# V1a.net
KiCad netlist of a schematic drawn in EAGLE
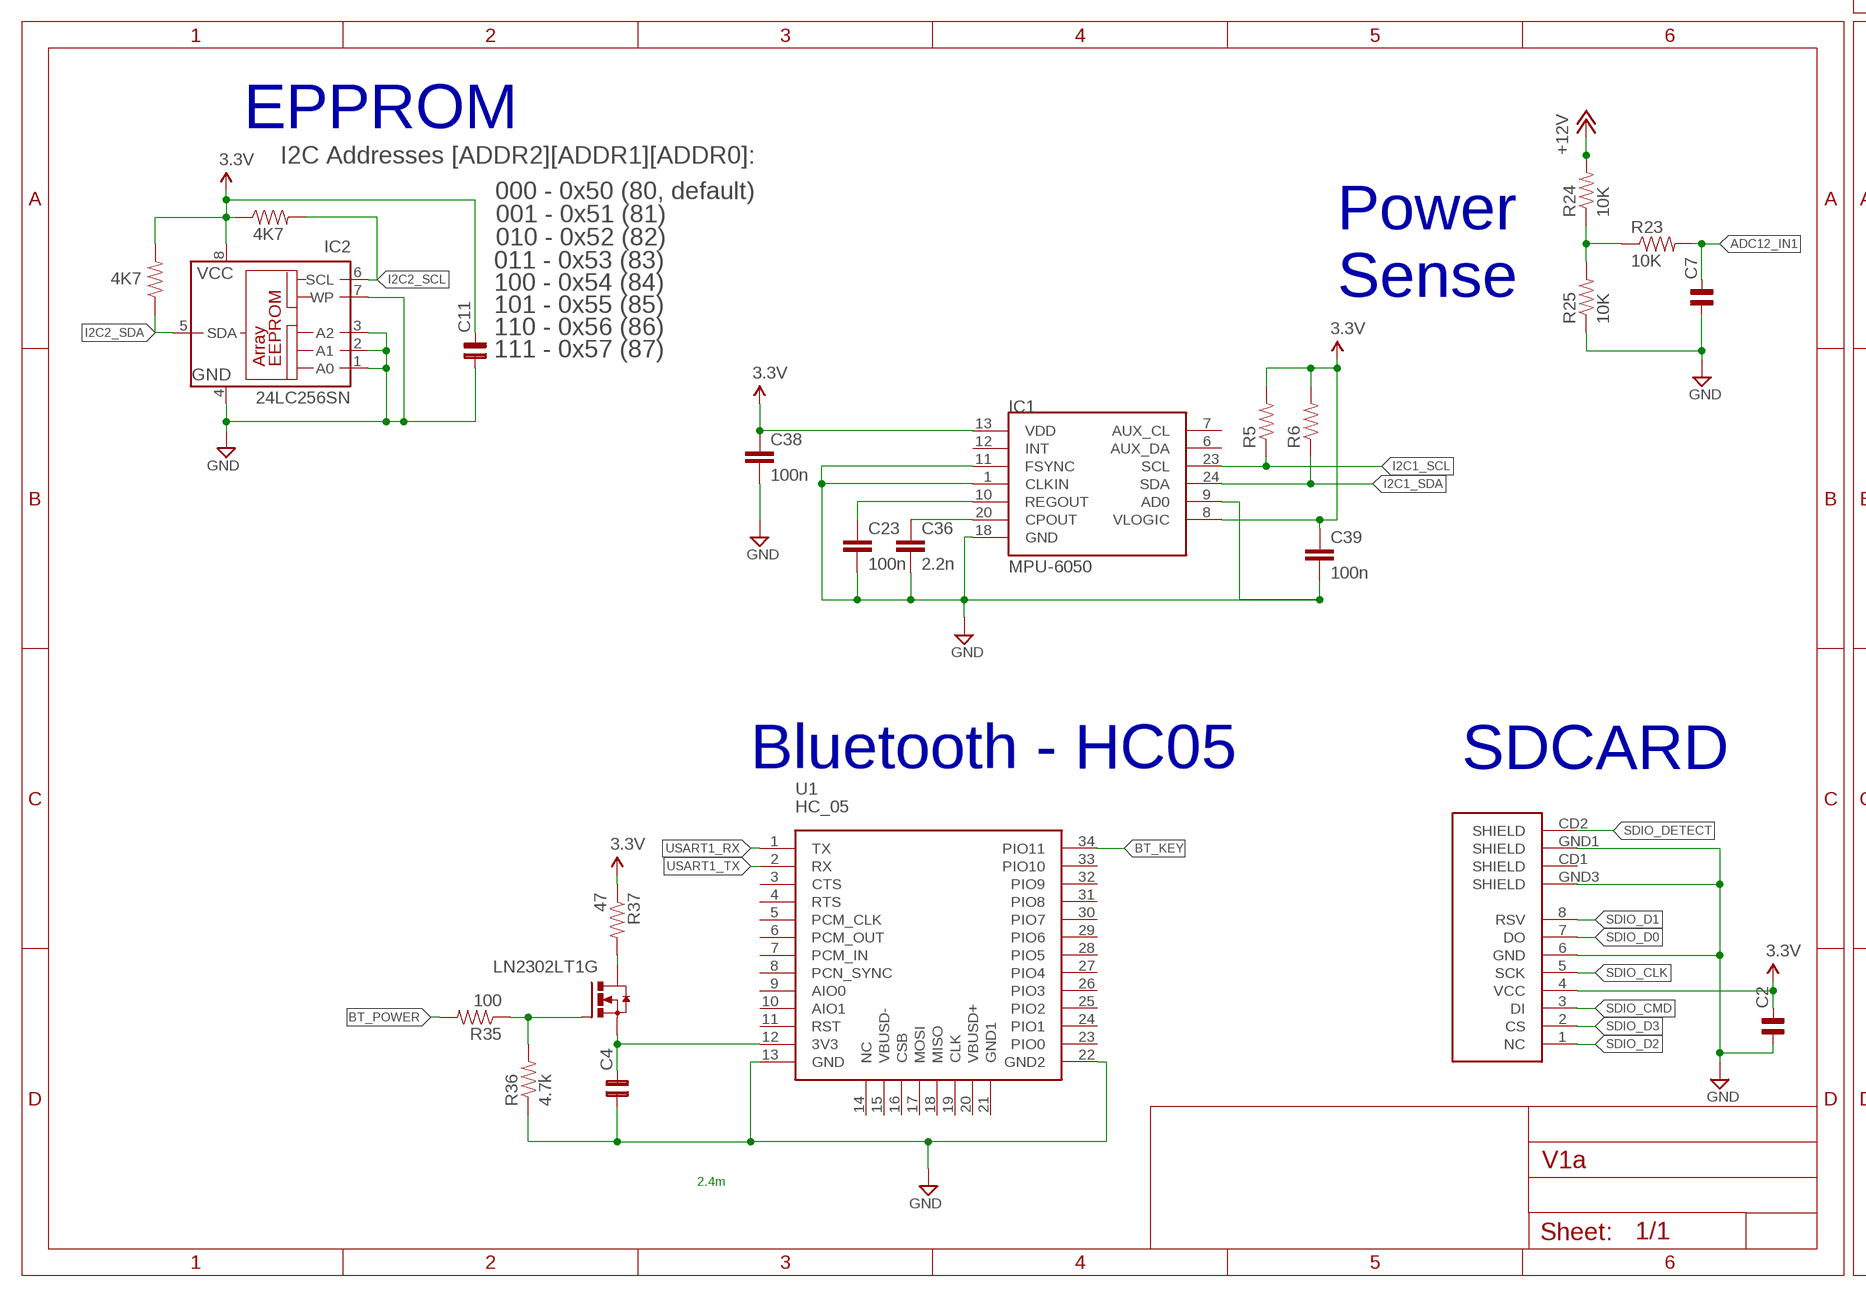
[diagram p0: schematic, sheet 1, part 1 of 2]
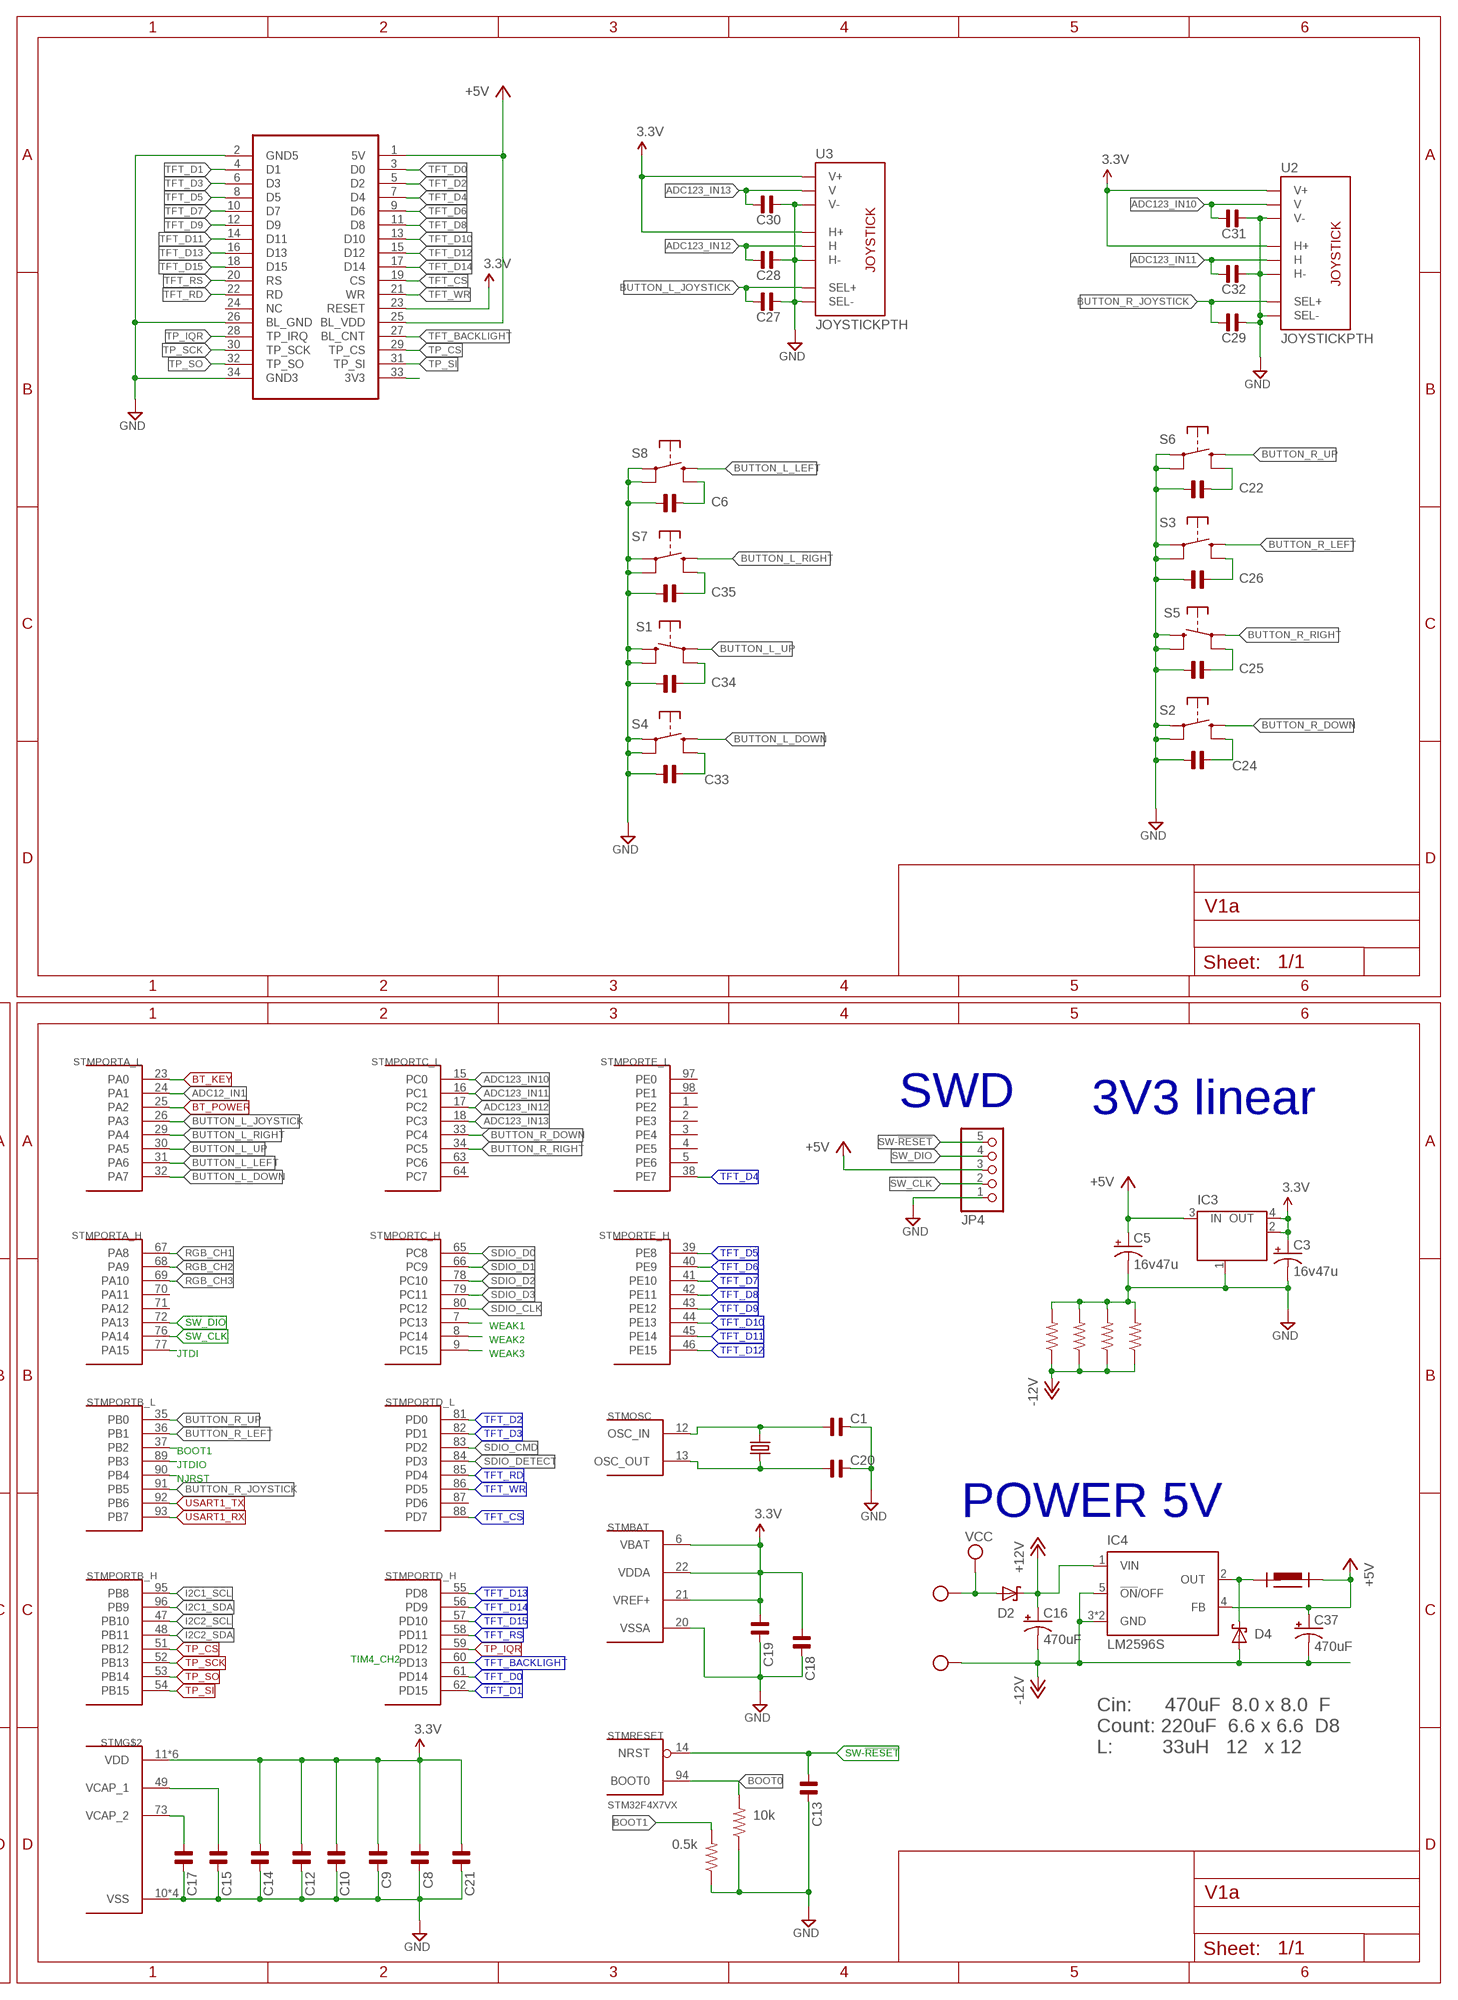
[diagram p1: schematic, sheet 1, part 2 of 2]

(export (version "E")
  (design (tool "Eeschema 10.0.6"))
  (components
    (comp (ref "C1")
      (value "C-NP-SMD-0603")
      (footprint "eagle-import:C-0603")
      (libsource (lib "eagle-import") (part "C-NP-SMD-0603"))
    )
    (comp (ref "C2")
      (value "C-NP-SMD-0603")
      (footprint "eagle-import:C-0603")
      (libsource (lib "eagle-import") (part "C-NP-SMD-0603"))
    )
    (comp (ref "C3")
      (value "16v47u")
      (footprint "eagle-import:SMC_C")
      (libsource (lib "eagle-import") (part "CPOL-USSMCC"))
    )
    (comp (ref "C4")
      (value "C-NP-SMD-0603")
      (footprint "eagle-import:C-0603")
      (libsource (lib "eagle-import") (part "C-NP-SMD-0603"))
    )
    (comp (ref "C5")
      (value "16v47u")
      (footprint "eagle-import:SMC_C")
      (libsource (lib "eagle-import") (part "CPOL-USSMCC"))
    )
    (comp (ref "C6")
      (value "C-NP-SMD-0603")
      (footprint "eagle-import:C-0603")
      (libsource (lib "eagle-import") (part "C-NP-SMD-0603"))
    )
    (comp (ref "C7")
      (value "C-NP-SMD-0603")
      (footprint "eagle-import:C-0603")
      (libsource (lib "eagle-import") (part "C-NP-SMD-0603"))
    )
    (comp (ref "C8")
      (value "C-NP-SMD-0603")
      (footprint "eagle-import:C-0603")
      (libsource (lib "eagle-import") (part "C-NP-SMD-0603"))
    )
    (comp (ref "C9")
      (value "C-NP-SMD-0603")
      (footprint "eagle-import:C-0603")
      (libsource (lib "eagle-import") (part "C-NP-SMD-0603"))
    )
    (comp (ref "C10")
      (value "C-NP-SMD-0603")
      (footprint "eagle-import:C-0603")
      (libsource (lib "eagle-import") (part "C-NP-SMD-0603"))
    )
    (comp (ref "C11")
      (value "C-NP-SMD-0603")
      (footprint "eagle-import:C-0603")
      (libsource (lib "eagle-import") (part "C-NP-SMD-0603"))
    )
    (comp (ref "C12")
      (value "C-NP-SMD-0603")
      (footprint "eagle-import:C-0603")
      (libsource (lib "eagle-import") (part "C-NP-SMD-0603"))
    )
    (comp (ref "C13")
      (value "C-NP-SMD-0603")
      (footprint "eagle-import:C-0603")
      (libsource (lib "eagle-import") (part "C-NP-SMD-0603"))
    )
    (comp (ref "C14")
      (value "C-NP-SMD-0603")
      (footprint "eagle-import:C-0603")
      (libsource (lib "eagle-import") (part "C-NP-SMD-0603"))
    )
    (comp (ref "C15")
      (value "C-NP-SMD-0603")
      (footprint "eagle-import:C-0603")
      (libsource (lib "eagle-import") (part "C-NP-SMD-0603"))
    )
    (comp (ref "C16")
      (value "470uF")
      (footprint "eagle-import:175TMP-0808")
      (libsource (lib "eagle-import") (part "CPOL-US175TMP-0808"))
    )
    (comp (ref "C17")
      (value "C-NP-SMD-0603")
      (footprint "eagle-import:C-0603")
      (libsource (lib "eagle-import") (part "C-NP-SMD-0603"))
    )
    (comp (ref "C18")
      (value "C-NP-SMD-0603")
      (footprint "eagle-import:C-0603")
      (libsource (lib "eagle-import") (part "C-NP-SMD-0603"))
    )
    (comp (ref "C19")
      (value "C-NP-SMD-0603")
      (footprint "eagle-import:C-0603")
      (libsource (lib "eagle-import") (part "C-NP-SMD-0603"))
    )
    (comp (ref "C20")
      (value "C-NP-SMD-0603")
      (footprint "eagle-import:C-0603")
      (libsource (lib "eagle-import") (part "C-NP-SMD-0603"))
    )
    (comp (ref "C21")
      (value "C-NP-SMD-0603")
      (footprint "eagle-import:C-0603")
      (libsource (lib "eagle-import") (part "C-NP-SMD-0603"))
    )
    (comp (ref "C22")
      (value "C-NP-SMD-0603")
      (footprint "eagle-import:C-0603")
      (libsource (lib "eagle-import") (part "C-NP-SMD-0603"))
    )
    (comp (ref "C23")
      (value "100n")
      (footprint "eagle-import:SPARKFUN_0603-CAP")
      (libsource (lib "eagle-import") (part "SPARKFUN_CAP0603-CAP"))
    )
    (comp (ref "C24")
      (value "C-NP-SMD-0603")
      (footprint "eagle-import:C-0603")
      (libsource (lib "eagle-import") (part "C-NP-SMD-0603"))
    )
    (comp (ref "C25")
      (value "C-NP-SMD-0603")
      (footprint "eagle-import:C-0603")
      (libsource (lib "eagle-import") (part "C-NP-SMD-0603"))
    )
    (comp (ref "C26")
      (value "C-NP-SMD-0603")
      (footprint "eagle-import:C-0603")
      (libsource (lib "eagle-import") (part "C-NP-SMD-0603"))
    )
    (comp (ref "C27")
      (value "C-NP-SMD-0603")
      (footprint "eagle-import:C-0603")
      (libsource (lib "eagle-import") (part "C-NP-SMD-0603"))
    )
    (comp (ref "C28")
      (value "C-NP-SMD-0603")
      (footprint "eagle-import:C-0603")
      (libsource (lib "eagle-import") (part "C-NP-SMD-0603"))
    )
    (comp (ref "C29")
      (value "C-NP-SMD-0603")
      (footprint "eagle-import:C-0603")
      (libsource (lib "eagle-import") (part "C-NP-SMD-0603"))
    )
    (comp (ref "C30")
      (value "C-NP-SMD-0603")
      (footprint "eagle-import:C-0603")
      (libsource (lib "eagle-import") (part "C-NP-SMD-0603"))
    )
    (comp (ref "C31")
      (value "C-NP-SMD-0603")
      (footprint "eagle-import:C-0603")
      (libsource (lib "eagle-import") (part "C-NP-SMD-0603"))
    )
    (comp (ref "C32")
      (value "C-NP-SMD-0603")
      (footprint "eagle-import:C-0603")
      (libsource (lib "eagle-import") (part "C-NP-SMD-0603"))
    )
    (comp (ref "C33")
      (value "C-NP-SMD-0603")
      (footprint "eagle-import:C-0603")
      (libsource (lib "eagle-import") (part "C-NP-SMD-0603"))
    )
    (comp (ref "C34")
      (value "C-NP-SMD-0603")
      (footprint "eagle-import:C-0603")
      (libsource (lib "eagle-import") (part "C-NP-SMD-0603"))
    )
    (comp (ref "C35")
      (value "C-NP-SMD-0603")
      (footprint "eagle-import:C-0603")
      (libsource (lib "eagle-import") (part "C-NP-SMD-0603"))
    )
    (comp (ref "C36")
      (value "2.2n")
      (footprint "eagle-import:SPARKFUN_0603-CAP")
      (libsource (lib "eagle-import") (part "SPARKFUN_CAP0603-CAP"))
    )
    (comp (ref "C37")
      (value "470uF")
      (footprint "eagle-import:E_7260-38W")
      (libsource (lib "eagle-import") (part "CPOL-USE/7260-38W"))
    )
    (comp (ref "C38")
      (value "100n")
      (footprint "eagle-import:SPARKFUN_0603-CAP")
      (libsource (lib "eagle-import") (part "SPARKFUN_CAP0603-CAP"))
    )
    (comp (ref "C39")
      (value "100n")
      (footprint "eagle-import:SPARKFUN_0603-CAP")
      (libsource (lib "eagle-import") (part "SPARKFUN_CAP0603-CAP"))
    )
    (comp (ref "D2")
      (value "MBRS330T3")
      (footprint "eagle-import:SMC")
      (libsource (lib "eagle-import") (part "MBRS30T33"))
    )
    (comp (ref "D4")
      (value "MBRS330T3")
      (footprint "eagle-import:SMC")
      (libsource (lib "eagle-import") (part "MBRS30T33"))
    )
    (comp (ref "IC1")
      (value "MPU-6050")
      (footprint "eagle-import:TESTING_QFN-24-4MM2")
      (libsource (lib "eagle-import") (part "TESTING_MPU-6050-1"))
    )
    (comp (ref "IC2")
      (value "24LC256SN")
      (footprint "eagle-import:SO-08")
      (fields (field (name "MF") "MICROCHIP") (field (name "MPN") "24LC256-I/SN"))
      (libsource (lib "eagle-import") (part "24SNLC256"))
    )
    (comp (ref "IC3")
      (value "LINEAR_MC33269ST-3.3T3")
      (footprint "eagle-import:LINEAR_SOT223")
      (libsource (lib "eagle-import") (part "LINEAR_MC33269ST-3.3T3"))
    )
    (comp (ref "IC4")
      (value "LM2596S")
      (footprint "eagle-import:TO263-5")
      (fields (field (name "MF") "NATIONAL SEMICONDUCTOR") (field (name "MPN") "LM2596S-ADJ/NOPB"))
      (libsource (lib "eagle-import") (part "LM2596S"))
    )
    (comp (ref "JP4")
      (value "PINHD-1X5_2.54-90°")
      (footprint "eagle-import:1X05_90")
      (libsource (lib "eagle-import") (part "PINHD-1X5_2.54-90°"))
    )
    (comp (ref "LN2302LT1G")
      (value "FDN327N")
      (footprint "eagle-import:SOT-23")
      (libsource (lib "eagle-import") (part "FDN327N"))
    )
    (comp (ref "R1")
      (value "10k")
      (footprint "eagle-import:SPARKFUN_0603-RES")
      (libsource (lib "eagle-import") (part "Robotech_RCL_SPARKFUN_RESISTOR0603-RES"))
    )
    (comp (ref "R2")
      (value "10k")
      (footprint "eagle-import:SPARKFUN_0603-RES")
      (libsource (lib "eagle-import") (part "Robotech_RCL_SPARKFUN_RESISTOR0603-RES"))
    )
    (comp (ref "R3")
      (value "10k")
      (footprint "eagle-import:SPARKFUN_0603-RES")
      (libsource (lib "eagle-import") (part "Robotech_RCL_SPARKFUN_RESISTOR0603-RES"))
    )
    (comp (ref "R4")
      (value "10k")
      (footprint "eagle-import:SPARKFUN_0603-RES")
      (libsource (lib "eagle-import") (part "Robotech_RCL_SPARKFUN_RESISTOR0603-RES"))
    )
    (comp (ref "R5")
      (value "SPARKFUN_RESISTOR0603-RES")
      (footprint "eagle-import:SPARKFUN_0603-RES")
      (libsource (lib "eagle-import") (part "Helios_RLC_SPARKFUN_RESISTOR0603-RES"))
    )
    (comp (ref "R6")
      (value "SPARKFUN_RESISTOR0603-RES")
      (footprint "eagle-import:SPARKFUN_0603-RES")
      (libsource (lib "eagle-import") (part "Helios_RLC_SPARKFUN_RESISTOR0603-RES"))
    )
    (comp (ref "R7")
      (value "10k")
      (footprint "eagle-import:SPARKFUN_0603-RES")
      (libsource (lib "eagle-import") (part "Robotech_RCL_SPARKFUN_RESISTOR0603-RES"))
    )
    (comp (ref "R8")
      (value "0.5k")
      (footprint "eagle-import:SPARKFUN_0603-RES")
      (libsource (lib "eagle-import") (part "Robotech_RCL_SPARKFUN_RESISTOR0603-RES"))
    )
    (comp (ref "R15")
      (value "4K7")
      (footprint "eagle-import:SPARKFUN_0603-RES")
      (libsource (lib "eagle-import") (part "Robotech_RCL_SPARKFUN_RESISTOR0603-RES"))
    )
    (comp (ref "R16")
      (value "4K7")
      (footprint "eagle-import:SPARKFUN_0603-RES")
      (libsource (lib "eagle-import") (part "Robotech_RCL_SPARKFUN_RESISTOR0603-RES"))
    )
    (comp (ref "R23")
      (value "10K")
      (footprint "eagle-import:SPARKFUN_0603-RES")
      (libsource (lib "eagle-import") (part "Robotech_RCL_SPARKFUN_RESISTOR0603-RES"))
    )
    (comp (ref "R24")
      (value "10K")
      (footprint "eagle-import:SPARKFUN_0603-RES")
      (libsource (lib "eagle-import") (part "Robotech_RCL_SPARKFUN_RESISTOR0603-RES"))
    )
    (comp (ref "R25")
      (value "10K")
      (footprint "eagle-import:SPARKFUN_0603-RES")
      (libsource (lib "eagle-import") (part "Robotech_RCL_SPARKFUN_RESISTOR0603-RES"))
    )
    (comp (ref "R35")
      (value "100")
      (footprint "eagle-import:SPARKFUN_0603-RES")
      (libsource (lib "eagle-import") (part "SPARKFUN_RESISTOR0603-RES"))
    )
    (comp (ref "R36")
      (value "4.7k")
      (footprint "eagle-import:SPARKFUN_0603-RES")
      (libsource (lib "eagle-import") (part "SPARKFUN_RESISTOR0603-RES"))
    )
    (comp (ref "R37")
      (value "47")
      (footprint "eagle-import:SPARKFUN_0603-RES")
      (libsource (lib "eagle-import") (part "SPARKFUN_RESISTOR0603-RES"))
    )
    (comp (ref "S1")
      (value "RACON12/")
      (footprint "eagle-import:RACON12_")
      (libsource (lib "eagle-import") (part "RACON12/"))
    )
    (comp (ref "S2")
      (value "RACON12/")
      (footprint "eagle-import:RACON12_")
      (libsource (lib "eagle-import") (part "RACON12/"))
    )
    (comp (ref "S3")
      (value "RACON12/")
      (footprint "eagle-import:RACON12_")
      (libsource (lib "eagle-import") (part "RACON12/"))
    )
    (comp (ref "S4")
      (value "RACON12/")
      (footprint "eagle-import:RACON12_")
      (libsource (lib "eagle-import") (part "RACON12/"))
    )
    (comp (ref "S5")
      (value "RACON12/")
      (footprint "eagle-import:RACON12_")
      (libsource (lib "eagle-import") (part "RACON12/"))
    )
    (comp (ref "S6")
      (value "RACON12/")
      (footprint "eagle-import:RACON12_")
      (libsource (lib "eagle-import") (part "RACON12/"))
    )
    (comp (ref "S7")
      (value "RACON12/")
      (footprint "eagle-import:RACON12_")
      (libsource (lib "eagle-import") (part "RACON12/"))
    )
    (comp (ref "S8")
      (value "RACON12/")
      (footprint "eagle-import:RACON12_")
      (libsource (lib "eagle-import") (part "RACON12/"))
    )
    (comp (ref "SDCARD2")
      (value "microSD Socket")
      (footprint "eagle-import:MICRO-SD-SOCKET-PP")
      (libsource (lib "eagle-import") (part "USD-SOCKETNEW"))
    )
    (comp (ref "STM")
      (value "STM32F4X7VX")
      (footprint "eagle-import:TQFP100")
      (fields (field (name "PARTNO") "STM32F427VI"))
      (libsource (lib "eagle-import") (part "STM32F4X7VX"))
    )
    (comp (ref "U$3")
      (value "TFT3.2")
      (footprint "eagle-import:HY32D_2")
      (libsource (lib "eagle-import") (part "TFT3.2"))
    )
    (comp (ref "U$5")
      (value "BIG_INDUCTOR")
      (footprint "eagle-import:12X12")
      (libsource (lib "eagle-import") (part "BIG_INDUCTOR"))
    )
    (comp (ref "U1")
      (value "HC_05")
      (footprint "eagle-import:BLUETOOTH_SMD")
      (libsource (lib "eagle-import") (part "HC_05"))
    )
    (comp (ref "U2")
      (value "JOYSTICKPTH")
      (footprint "eagle-import:JOYSTICK")
      (libsource (lib "eagle-import") (part "JOYSTICKPTH"))
    )
    (comp (ref "U3")
      (value "JOYSTICKPTH")
      (footprint "eagle-import:JOYSTICK")
      (libsource (lib "eagle-import") (part "JOYSTICKPTH"))
    )
    (comp (ref "X1")
      (value "MKDSN1,5/2-5,08")
      (footprint "eagle-import:MKDSN1,5_2-5,08")
      (fields (field (name "MPN") "MKDSN 1,5/2-5.08"))
      (libsource (lib "eagle-import") (part "MKDSN1,5/2-5,08"))
    )
    (comp (ref "Y1")
      (value "CRYSTALHC49US")
      (footprint "eagle-import:HC49US")
      (libsource (lib "eagle-import") (part "CRYSTALHC49US"))
    )
  )
  (nets
    (net (code "1") (name "+5V") (class "Default")
      (node (ref "C37") (pin "+") (pinfunction "+_+") (pintype "passive"))
      (node (ref "C5") (pin "+") (pinfunction "+_+") (pintype "passive"))
      (node (ref "IC3") (pin "3") (pinfunction "IN_3") (pintype "input"))
      (node (ref "IC4") (pin "4") (pinfunction "FB_4") (pintype "input"))
      (node (ref "JP4") (pin "3") (pinfunction "3_3") (pintype "passive"))
      (node (ref "U$3") (pin "1") (pinfunction "5V_1") (pintype "bidirectional"))
      (node (ref "U$3") (pin "25") (pinfunction "BL_VDD_25") (pintype "bidirectional"))
      (node (ref "U$5") (pin "P$1") (pinfunction "P$1_P$1") (pintype "bidirectional"))
    )
    (net (code "2") (name "+12V") (class "Default")
      (node (ref "C16") (pin "+") (pinfunction "+_+") (pintype "passive"))
      (node (ref "D2") (pin "C") (pinfunction "C_C") (pintype "passive"))
      (node (ref "IC4") (pin "1") (pinfunction "VIN_1") (pintype "input"))
      (node (ref "R24") (pin "2") (pinfunction "2_2") (pintype "passive"))
    )
    (net (code "3") (name "-12V") (class "Default")
      (node (ref "C16") (pin "-") (pinfunction "-_-") (pintype "passive"))
      (node (ref "C37") (pin "-") (pinfunction "-_-") (pintype "passive"))
      (node (ref "D4") (pin "A") (pinfunction "A_A") (pintype "passive"))
      (node (ref "IC4") (pin "3") (pinfunction "GND_3") (pintype "power_in"))
      (node (ref "IC4") (pin "5") (pinfunction "~{ON}/OFF_5") (pintype "input"))
      (node (ref "IC4") (pin "6") (pinfunction "GND_6") (pintype "power_in"))
      (node (ref "R1") (pin "1") (pinfunction "1_1") (pintype "passive"))
      (node (ref "R2") (pin "1") (pinfunction "1_1") (pintype "passive"))
      (node (ref "R3") (pin "1") (pinfunction "1_1") (pintype "passive"))
      (node (ref "R4") (pin "1") (pinfunction "1_1") (pintype "passive"))
      (node (ref "X1") (pin "1") (pinfunction "KL_1") (pintype "passive"))
    )
    (net (code "4") (name "/JTDI") (class "Default")
      (node (ref "STM") (pin "77") (pinfunction "PA15_77") (pintype "bidirectional"))
    )
    (net (code "5") (name "/JTDIO") (class "Default")
      (node (ref "STM") (pin "89") (pinfunction "PB3_89") (pintype "bidirectional"))
    )
    (net (code "6") (name "/NJRST") (class "Default")
      (node (ref "STM") (pin "90") (pinfunction "PB4_90") (pintype "bidirectional"))
    )
    (net (code "7") (name "/SW-~{RESET}") (class "Default")
      (node (ref "C13") (pin "1") (pinfunction "1_1") (pintype "passive"))
      (node (ref "JP4") (pin "5") (pinfunction "5_5") (pintype "passive"))
      (node (ref "STM") (pin "14") (pinfunction "NRST_14") (pintype "input"))
    )
    (net (code "8") (name "/WEAK1") (class "Default")
      (node (ref "STM") (pin "7") (pinfunction "PC13_7") (pintype "bidirectional"))
    )
    (net (code "9") (name "/WEAK2") (class "Default")
      (node (ref "STM") (pin "8") (pinfunction "PC14_8") (pintype "bidirectional"))
    )
    (net (code "10") (name "/WEAK3") (class "Default")
      (node (ref "STM") (pin "9") (pinfunction "PC15_9") (pintype "bidirectional"))
    )
    (net (code "11") (name "3.3V") (class "Default")
      (node (ref "C10") (pin "1") (pinfunction "1_1") (pintype "passive"))
      (node (ref "C11") (pin "2") (pinfunction "2_2") (pintype "passive"))
      (node (ref "C12") (pin "1") (pinfunction "1_1") (pintype "passive"))
      (node (ref "C14") (pin "1") (pinfunction "1_1") (pintype "passive"))
      (node (ref "C18") (pin "1") (pinfunction "1_1") (pintype "passive"))
      (node (ref "C19") (pin "1") (pinfunction "1_1") (pintype "passive"))
      (node (ref "C2") (pin "2") (pinfunction "2_2") (pintype "passive"))
      (node (ref "C21") (pin "1") (pinfunction "1_1") (pintype "passive"))
      (node (ref "C3") (pin "+") (pinfunction "+_+") (pintype "passive"))
      (node (ref "C38") (pin "1") (pinfunction "1_1") (pintype "passive"))
      (node (ref "C39") (pin "1") (pinfunction "1_1") (pintype "passive"))
      (node (ref "C8") (pin "1") (pinfunction "1_1") (pintype "passive"))
      (node (ref "C9") (pin "1") (pinfunction "1_1") (pintype "passive"))
      (node (ref "IC1") (pin "13") (pinfunction "VDD_13") (pintype "bidirectional"))
      (node (ref "IC1") (pin "8") (pinfunction "VLOGIC_8") (pintype "bidirectional"))
      (node (ref "IC2") (pin "8") (pinfunction "VCC_8") (pintype "power_in"))
      (node (ref "IC3") (pin "2") (pinfunction "OUT_2") (pintype "passive"))
      (node (ref "IC3") (pin "4") (pinfunction "OUT_4") (pintype "passive"))
      (node (ref "R15") (pin "1") (pinfunction "1_1") (pintype "passive"))
      (node (ref "R16") (pin "2") (pinfunction "2_2") (pintype "passive"))
      (node (ref "R37") (pin "1") (pinfunction "1_1") (pintype "passive"))
      (node (ref "R5") (pin "2") (pinfunction "2_2") (pintype "passive"))
      (node (ref "R6") (pin "2") (pinfunction "2_2") (pintype "passive"))
      (node (ref "SDCARD2") (pin "4") (pinfunction "VCC_4") (pintype "bidirectional"))
      (node (ref "STM") (pin "100") (pinfunction "VDD_100") (pintype "power_in"))
      (node (ref "STM") (pin "11") (pinfunction "VDD_11") (pintype "power_in"))
      (node (ref "STM") (pin "19") (pinfunction "VDD_19") (pintype "power_in"))
      (node (ref "STM") (pin "21") (pinfunction "VREF+_21") (pintype "input"))
      (node (ref "STM") (pin "22") (pinfunction "VDDA_22") (pintype "power_in"))
      (node (ref "STM") (pin "28") (pinfunction "VDD_28") (pintype "power_in"))
      (node (ref "STM") (pin "50") (pinfunction "VDD_50") (pintype "power_in"))
      (node (ref "STM") (pin "6") (pinfunction "VBAT_6") (pintype "power_in"))
      (node (ref "STM") (pin "75") (pinfunction "VDD_75") (pintype "power_in"))
      (node (ref "U$3") (pin "23") (pinfunction "RESET_23") (pintype "bidirectional"))
      (node (ref "U2") (pin "H1") (pinfunction "H+_H1") (pintype "bidirectional"))
      (node (ref "U2") (pin "V1") (pinfunction "V+_V1") (pintype "bidirectional"))
      (node (ref "U3") (pin "H1") (pinfunction "H+_H1") (pintype "bidirectional"))
      (node (ref "U3") (pin "V1") (pinfunction "V+_V1") (pintype "bidirectional"))
    )
    (net (code "12") (name "ADC12_IN1") (class "Default")
      (node (ref "C7") (pin "2") (pinfunction "2_2") (pintype "passive"))
      (node (ref "R23") (pin "2") (pinfunction "2_2") (pintype "passive"))
      (node (ref "STM") (pin "24") (pinfunction "PA1_24") (pintype "bidirectional"))
    )
    (net (code "13") (name "ADC123_IN10") (class "Default")
      (node (ref "C31") (pin "1") (pinfunction "1_1") (pintype "passive"))
      (node (ref "STM") (pin "15") (pinfunction "PC0_15") (pintype "bidirectional"))
      (node (ref "U2") (pin "V2") (pinfunction "V_V2") (pintype "bidirectional"))
    )
    (net (code "14") (name "ADC123_IN11") (class "Default")
      (node (ref "C32") (pin "1") (pinfunction "1_1") (pintype "passive"))
      (node (ref "STM") (pin "16") (pinfunction "PC1_16") (pintype "bidirectional"))
      (node (ref "U2") (pin "H2") (pinfunction "H_H2") (pintype "bidirectional"))
    )
    (net (code "15") (name "ADC123_IN12") (class "Default")
      (node (ref "C28") (pin "1") (pinfunction "1_1") (pintype "passive"))
      (node (ref "STM") (pin "17") (pinfunction "PC2_17") (pintype "bidirectional"))
      (node (ref "U3") (pin "H2") (pinfunction "H_H2") (pintype "bidirectional"))
    )
    (net (code "16") (name "ADC123_IN13") (class "Default")
      (node (ref "C30") (pin "1") (pinfunction "1_1") (pintype "passive"))
      (node (ref "STM") (pin "18") (pinfunction "PC3_18") (pintype "bidirectional"))
      (node (ref "U3") (pin "V2") (pinfunction "V_V2") (pintype "bidirectional"))
    )
    (net (code "17") (name "BOOT0") (class "Default")
      (node (ref "R7") (pin "2") (pinfunction "2_2") (pintype "passive"))
      (node (ref "STM") (pin "94") (pinfunction "BOOT0_94") (pintype "input"))
    )
    (net (code "18") (name "BOOT1") (class "Default")
      (node (ref "R8") (pin "2") (pinfunction "2_2") (pintype "passive"))
      (node (ref "STM") (pin "37") (pinfunction "PB2_37") (pintype "bidirectional"))
    )
    (net (code "19") (name "BT_KEY") (class "Default")
      (node (ref "STM") (pin "23") (pinfunction "PA0_23") (pintype "bidirectional"))
      (node (ref "U1") (pin "34") (pinfunction "PIO11_34") (pintype "bidirectional"))
    )
    (net (code "20") (name "BT_POWER") (class "Default")
      (node (ref "R35") (pin "2") (pinfunction "2_2") (pintype "passive"))
      (node (ref "STM") (pin "25") (pinfunction "PA2_25") (pintype "bidirectional"))
    )
    (net (code "21") (name "BUTTON_L_DOWN") (class "Default")
      (node (ref "S4") (pin "1") (pinfunction "S_1") (pintype "passive"))
      (node (ref "STM") (pin "32") (pinfunction "PA7_32") (pintype "bidirectional"))
    )
    (net (code "22") (name "BUTTON_L_JOYSTICK") (class "Default")
      (node (ref "C27") (pin "1") (pinfunction "1_1") (pintype "passive"))
      (node (ref "STM") (pin "26") (pinfunction "PA3_26") (pintype "bidirectional"))
      (node (ref "U3") (pin "B1A") (pinfunction "SEL+_B1A") (pintype "bidirectional"))
    )
    (net (code "23") (name "BUTTON_L_LEFT") (class "Default")
      (node (ref "S8") (pin "1") (pinfunction "S_1") (pintype "passive"))
      (node (ref "STM") (pin "31") (pinfunction "PA6_31") (pintype "bidirectional"))
    )
    (net (code "24") (name "BUTTON_L_RIGHT") (class "Default")
      (node (ref "S7") (pin "1") (pinfunction "S_1") (pintype "passive"))
      (node (ref "STM") (pin "29") (pinfunction "PA4_29") (pintype "bidirectional"))
    )
    (net (code "25") (name "BUTTON_L_UP") (class "Default")
      (node (ref "S1") (pin "3") (pinfunction "P_3") (pintype "passive"))
      (node (ref "STM") (pin "30") (pinfunction "PA5_30") (pintype "bidirectional"))
    )
    (net (code "26") (name "BUTTON_R_DOWN") (class "Default")
      (node (ref "S2") (pin "1") (pinfunction "S_1") (pintype "passive"))
      (node (ref "STM") (pin "33") (pinfunction "PC4_33") (pintype "bidirectional"))
    )
    (net (code "27") (name "BUTTON_R_JOYSTICK") (class "Default")
      (node (ref "C29") (pin "1") (pinfunction "1_1") (pintype "passive"))
      (node (ref "STM") (pin "91") (pinfunction "PB5_91") (pintype "bidirectional"))
      (node (ref "U2") (pin "B1A") (pinfunction "SEL+_B1A") (pintype "bidirectional"))
    )
    (net (code "28") (name "BUTTON_R_LEFT") (class "Default")
      (node (ref "S3") (pin "1") (pinfunction "S_1") (pintype "passive"))
      (node (ref "STM") (pin "36") (pinfunction "PB1_36") (pintype "bidirectional"))
    )
    (net (code "29") (name "BUTTON_R_RIGHT") (class "Default")
      (node (ref "S5") (pin "3") (pinfunction "P_3") (pintype "passive"))
      (node (ref "STM") (pin "34") (pinfunction "PC5_34") (pintype "bidirectional"))
    )
    (net (code "30") (name "BUTTON_R_UP") (class "Default")
      (node (ref "S6") (pin "1") (pinfunction "S_1") (pintype "passive"))
      (node (ref "STM") (pin "35") (pinfunction "PB0_35") (pintype "bidirectional"))
    )
    (net (code "31") (name "GND") (class "Default")
      (node (ref "C1") (pin "2") (pinfunction "2_2") (pintype "passive"))
      (node (ref "C10") (pin "2") (pinfunction "2_2") (pintype "passive"))
      (node (ref "C11") (pin "1") (pinfunction "1_1") (pintype "passive"))
      (node (ref "C12") (pin "2") (pinfunction "2_2") (pintype "passive"))
      (node (ref "C13") (pin "2") (pinfunction "2_2") (pintype "passive"))
      (node (ref "C14") (pin "2") (pinfunction "2_2") (pintype "passive"))
      (node (ref "C15") (pin "2") (pinfunction "2_2") (pintype "passive"))
      (node (ref "C17") (pin "2") (pinfunction "2_2") (pintype "passive"))
      (node (ref "C18") (pin "2") (pinfunction "2_2") (pintype "passive"))
      (node (ref "C19") (pin "2") (pinfunction "2_2") (pintype "passive"))
      (node (ref "C2") (pin "1") (pinfunction "1_1") (pintype "passive"))
      (node (ref "C20") (pin "2") (pinfunction "2_2") (pintype "passive"))
      (node (ref "C21") (pin "2") (pinfunction "2_2") (pintype "passive"))
      (node (ref "C22") (pin "1") (pinfunction "1_1") (pintype "passive"))
      (node (ref "C23") (pin "2") (pinfunction "2_2") (pintype "passive"))
      (node (ref "C24") (pin "2") (pinfunction "2_2") (pintype "passive"))
      (node (ref "C25") (pin "2") (pinfunction "2_2") (pintype "passive"))
      (node (ref "C26") (pin "2") (pinfunction "2_2") (pintype "passive"))
      (node (ref "C27") (pin "2") (pinfunction "2_2") (pintype "passive"))
      (node (ref "C28") (pin "2") (pinfunction "2_2") (pintype "passive"))
      (node (ref "C29") (pin "2") (pinfunction "2_2") (pintype "passive"))
      (node (ref "C3") (pin "-") (pinfunction "-_-") (pintype "passive"))
      (node (ref "C30") (pin "2") (pinfunction "2_2") (pintype "passive"))
      (node (ref "C31") (pin "2") (pinfunction "2_2") (pintype "passive"))
      (node (ref "C32") (pin "2") (pinfunction "2_2") (pintype "passive"))
      (node (ref "C33") (pin "2") (pinfunction "2_2") (pintype "passive"))
      (node (ref "C34") (pin "2") (pinfunction "2_2") (pintype "passive"))
      (node (ref "C35") (pin "2") (pinfunction "2_2") (pintype "passive"))
      (node (ref "C36") (pin "2") (pinfunction "2_2") (pintype "passive"))
      (node (ref "C38") (pin "2") (pinfunction "2_2") (pintype "passive"))
      (node (ref "C39") (pin "2") (pinfunction "2_2") (pintype "passive"))
      (node (ref "C4") (pin "1") (pinfunction "1_1") (pintype "passive"))
      (node (ref "C5") (pin "-") (pinfunction "-_-") (pintype "passive"))
      (node (ref "C6") (pin "1") (pinfunction "1_1") (pintype "passive"))
      (node (ref "C7") (pin "1") (pinfunction "1_1") (pintype "passive"))
      (node (ref "C8") (pin "2") (pinfunction "2_2") (pintype "passive"))
      (node (ref "C9") (pin "2") (pinfunction "2_2") (pintype "passive"))
      (node (ref "IC1") (pin "1") (pinfunction "CLKIN_1") (pintype "bidirectional"))
      (node (ref "IC1") (pin "11") (pinfunction "FSYNC_11") (pintype "bidirectional"))
      (node (ref "IC1") (pin "18") (pinfunction "GND_18") (pintype "bidirectional"))
      (node (ref "IC1") (pin "9") (pinfunction "AD0_9") (pintype "bidirectional"))
      (node (ref "IC2") (pin "1") (pinfunction "A0_1") (pintype "input"))
      (node (ref "IC2") (pin "2") (pinfunction "A1_2") (pintype "input"))
      (node (ref "IC2") (pin "3") (pinfunction "A2_3") (pintype "input"))
      (node (ref "IC2") (pin "4") (pinfunction "GND_4") (pintype "power_in"))
      (node (ref "IC2") (pin "7") (pinfunction "WP_7") (pintype "input"))
      (node (ref "IC3") (pin "1") (pinfunction "GND/ADJ_1") (pintype "input"))
      (node (ref "JP4") (pin "1") (pinfunction "1_1") (pintype "passive"))
      (node (ref "R1") (pin "2") (pinfunction "2_2") (pintype "passive"))
      (node (ref "R2") (pin "2") (pinfunction "2_2") (pintype "passive"))
      (node (ref "R25") (pin "1") (pinfunction "1_1") (pintype "passive"))
      (node (ref "R3") (pin "2") (pinfunction "2_2") (pintype "passive"))
      (node (ref "R36") (pin "1") (pinfunction "1_1") (pintype "passive"))
      (node (ref "R4") (pin "2") (pinfunction "2_2") (pintype "passive"))
      (node (ref "R7") (pin "1") (pinfunction "1_1") (pintype "passive"))
      (node (ref "R8") (pin "1") (pinfunction "1_1") (pintype "passive"))
      (node (ref "S1") (pin "1") (pinfunction "S_1") (pintype "passive"))
      (node (ref "S1") (pin "2") (pinfunction "S_2") (pintype "passive"))
      (node (ref "S2") (pin "3") (pinfunction "P_3") (pintype "passive"))
      (node (ref "S2") (pin "4") (pinfunction "P_4") (pintype "passive"))
      (node (ref "S3") (pin "3") (pinfunction "P_3") (pintype "passive"))
      (node (ref "S3") (pin "4") (pinfunction "P_4") (pintype "passive"))
      (node (ref "S4") (pin "3") (pinfunction "P_3") (pintype "passive"))
      (node (ref "S4") (pin "4") (pinfunction "P_4") (pintype "passive"))
      (node (ref "S5") (pin "1") (pinfunction "S_1") (pintype "passive"))
      (node (ref "S5") (pin "2") (pinfunction "S_2") (pintype "passive"))
      (node (ref "S6") (pin "3") (pinfunction "P_3") (pintype "passive"))
      (node (ref "S6") (pin "4") (pinfunction "P_4") (pintype "passive"))
      (node (ref "S7") (pin "3") (pinfunction "P_3") (pintype "passive"))
      (node (ref "S7") (pin "4") (pinfunction "P_4") (pintype "passive"))
      (node (ref "S8") (pin "3") (pinfunction "P_3") (pintype "passive"))
      (node (ref "S8") (pin "4") (pinfunction "P_4") (pintype "passive"))
      (node (ref "SDCARD2") (pin "6") (pinfunction "GND_6") (pintype "bidirectional"))
      (node (ref "SDCARD2") (pin "GND1") (pinfunction "SHIELD_GND1") (pintype "bidirectional"))
      (node (ref "SDCARD2") (pin "GND3") (pinfunction "SHIELD_GND3") (pintype "bidirectional"))
      (node (ref "STM") (pin "10") (pinfunction "VSS_10") (pintype "power_in"))
      (node (ref "STM") (pin "20") (pinfunction "VSSA_20") (pintype "power_in"))
      (node (ref "STM") (pin "27") (pinfunction "VSS_27") (pintype "power_in"))
      (node (ref "STM") (pin "74") (pinfunction "VSS_74") (pintype "power_in"))
      (node (ref "STM") (pin "99") (pinfunction "VSS_99") (pintype "power_in"))
      (node (ref "U$3") (pin "2") (pinfunction "GND5_2") (pintype "bidirectional"))
      (node (ref "U$3") (pin "26") (pinfunction "BL_GND_26") (pintype "bidirectional"))
      (node (ref "U$3") (pin "34") (pinfunction "GND3_34") (pintype "bidirectional"))
      (node (ref "U1") (pin "13") (pinfunction "GND_13") (pintype "bidirectional"))
      (node (ref "U1") (pin "22") (pinfunction "GND2_22") (pintype "bidirectional"))
      (node (ref "U2") (pin "B2A") (pinfunction "SEL-_B2A") (pintype "bidirectional"))
      (node (ref "U2") (pin "H3") (pinfunction "H-_H3") (pintype "bidirectional"))
      (node (ref "U2") (pin "V3") (pinfunction "V-_V3") (pintype "bidirectional"))
      (node (ref "U3") (pin "B2A") (pinfunction "SEL-_B2A") (pintype "bidirectional"))
      (node (ref "U3") (pin "H3") (pinfunction "H-_H3") (pintype "bidirectional"))
      (node (ref "U3") (pin "V3") (pinfunction "V-_V3") (pintype "bidirectional"))
    )
    (net (code "32") (name "I2C1_SCL") (class "Default")
      (node (ref "IC1") (pin "23") (pinfunction "SCL_23") (pintype "bidirectional"))
      (node (ref "R5") (pin "1") (pinfunction "1_1") (pintype "passive"))
      (node (ref "STM") (pin "95") (pinfunction "PB8_95") (pintype "bidirectional"))
    )
    (net (code "33") (name "I2C1_SDA") (class "Default")
      (node (ref "IC1") (pin "24") (pinfunction "SDA_24") (pintype "bidirectional"))
      (node (ref "R6") (pin "1") (pinfunction "1_1") (pintype "passive"))
      (node (ref "STM") (pin "96") (pinfunction "PB9_96") (pintype "bidirectional"))
    )
    (net (code "34") (name "I2C2_SCL") (class "Default")
      (node (ref "IC2") (pin "6") (pinfunction "SCL_6") (pintype "input"))
      (node (ref "R15") (pin "2") (pinfunction "2_2") (pintype "passive"))
      (node (ref "STM") (pin "47") (pinfunction "PB10_47") (pintype "bidirectional"))
    )
    (net (code "35") (name "I2C2_SDA") (class "Default")
      (node (ref "IC2") (pin "5") (pinfunction "SDA_5") (pintype "bidirectional"))
      (node (ref "R16") (pin "1") (pinfunction "1_1") (pintype "passive"))
      (node (ref "STM") (pin "48") (pinfunction "PB11_48") (pintype "bidirectional"))
    )
    (net (code "36") (name "Net-(C6-Pad2)") (class "Default")
      (node (ref "C6") (pin "2") (pinfunction "2_2") (pintype "passive"))
      (node (ref "S8") (pin "2") (pinfunction "S_2") (pintype "passive"))
    )
    (net (code "37") (name "Net-(C22-Pad2)") (class "Default")
      (node (ref "C22") (pin "2") (pinfunction "2_2") (pintype "passive"))
      (node (ref "S6") (pin "2") (pinfunction "S_2") (pintype "passive"))
    )
    (net (code "38") (name "Net-(C24-Pad1)") (class "Default")
      (node (ref "C24") (pin "1") (pinfunction "1_1") (pintype "passive"))
      (node (ref "S2") (pin "2") (pinfunction "S_2") (pintype "passive"))
    )
    (net (code "39") (name "Net-(C25-Pad1)") (class "Default")
      (node (ref "C25") (pin "1") (pinfunction "1_1") (pintype "passive"))
      (node (ref "S5") (pin "4") (pinfunction "P_4") (pintype "passive"))
    )
    (net (code "40") (name "Net-(C26-Pad1)") (class "Default")
      (node (ref "C26") (pin "1") (pinfunction "1_1") (pintype "passive"))
      (node (ref "S3") (pin "2") (pinfunction "S_2") (pintype "passive"))
    )
    (net (code "41") (name "Net-(C33-Pad1)") (class "Default")
      (node (ref "C33") (pin "1") (pinfunction "1_1") (pintype "passive"))
      (node (ref "S4") (pin "2") (pinfunction "S_2") (pintype "passive"))
    )
    (net (code "42") (name "Net-(C34-Pad1)") (class "Default")
      (node (ref "C34") (pin "1") (pinfunction "1_1") (pintype "passive"))
      (node (ref "S1") (pin "4") (pinfunction "P_4") (pintype "passive"))
    )
    (net (code "43") (name "Net-(C35-Pad1)") (class "Default")
      (node (ref "C35") (pin "1") (pinfunction "1_1") (pintype "passive"))
      (node (ref "S7") (pin "2") (pinfunction "S_2") (pintype "passive"))
    )
    (net (code "44") (name "Net-(IC1-CPOUT)") (class "Default")
      (node (ref "C36") (pin "1") (pinfunction "1_1") (pintype "passive"))
      (node (ref "IC1") (pin "20") (pinfunction "CPOUT_20") (pintype "bidirectional"))
    )
    (net (code "45") (name "Net-(IC1-REGOUT)") (class "Default")
      (node (ref "C23") (pin "1") (pinfunction "1_1") (pintype "passive"))
      (node (ref "IC1") (pin "10") (pinfunction "REGOUT_10") (pintype "bidirectional"))
    )
    (net (code "46") (name "Net-(IC4-OUT)") (class "Default")
      (node (ref "D4") (pin "C") (pinfunction "C_C") (pintype "passive"))
      (node (ref "IC4") (pin "2") (pinfunction "OUT_2") (pintype "output"))
      (node (ref "U$5") (pin "P$2") (pinfunction "P$2_P$2") (pintype "bidirectional"))
    )
    (net (code "47") (name "Net-(LN2302LT1G-D)") (class "Default")
      (node (ref "LN2302LT1G") (pin "3") (pinfunction "D_3") (pintype "passive"))
      (node (ref "R37") (pin "2") (pinfunction "2_2") (pintype "passive"))
    )
    (net (code "48") (name "Net-(LN2302LT1G-G)") (class "Default")
      (node (ref "LN2302LT1G") (pin "1") (pinfunction "G_1") (pintype "passive"))
      (node (ref "R35") (pin "1") (pinfunction "1_1") (pintype "passive"))
      (node (ref "R36") (pin "2") (pinfunction "2_2") (pintype "passive"))
    )
    (net (code "49") (name "Net-(LN2302LT1G-S)") (class "Default")
      (node (ref "C4") (pin "2") (pinfunction "2_2") (pintype "passive"))
      (node (ref "LN2302LT1G") (pin "2") (pinfunction "S_2") (pintype "passive"))
      (node (ref "U1") (pin "12") (pinfunction "3V3_12") (pintype "bidirectional"))
    )
    (net (code "50") (name "Net-(R23-Pad1)") (class "Default")
      (node (ref "R23") (pin "1") (pinfunction "1_1") (pintype "passive"))
      (node (ref "R24") (pin "1") (pinfunction "1_1") (pintype "passive"))
      (node (ref "R25") (pin "2") (pinfunction "2_2") (pintype "passive"))
    )
    (net (code "51") (name "Net-(STMB-VCAP_1)") (class "Default")
      (node (ref "C15") (pin "1") (pinfunction "1_1") (pintype "passive"))
      (node (ref "STM") (pin "49") (pinfunction "VCAP_1_49") (pintype "power_in"))
    )
    (net (code "52") (name "Net-(STMB-VCAP_2)") (class "Default")
      (node (ref "C17") (pin "1") (pinfunction "1_1") (pintype "passive"))
      (node (ref "STM") (pin "73") (pinfunction "VCAP_2_73") (pintype "power_in"))
    )
    (net (code "53") (name "Net-(STMC-OSC_IN)") (class "Default")
      (node (ref "C1") (pin "1") (pinfunction "1_1") (pintype "passive"))
      (node (ref "STM") (pin "12") (pinfunction "OSC_IN_12") (pintype "input"))
      (node (ref "Y1") (pin "2") (pinfunction "2_2") (pintype "passive"))
    )
    (net (code "54") (name "Net-(STMC-OSC_OUT)") (class "Default")
      (node (ref "C20") (pin "1") (pinfunction "1_1") (pintype "passive"))
      (node (ref "STM") (pin "13") (pinfunction "OSC_OUT_13") (pintype "output"))
      (node (ref "Y1") (pin "1") (pinfunction "1_1") (pintype "passive"))
    )
    (net (code "55") (name "RGB_CH1") (class "Default")
      (node (ref "STM") (pin "67") (pinfunction "PA8_67") (pintype "bidirectional"))
    )
    (net (code "56") (name "RGB_CH2") (class "Default")
      (node (ref "STM") (pin "68") (pinfunction "PA9_68") (pintype "bidirectional"))
    )
    (net (code "57") (name "RGB_CH3") (class "Default")
      (node (ref "STM") (pin "69") (pinfunction "PA10_69") (pintype "bidirectional"))
    )
    (net (code "58") (name "SDIO_CLK") (class "Default")
      (node (ref "SDCARD2") (pin "5") (pinfunction "SCK_5") (pintype "bidirectional"))
      (node (ref "STM") (pin "80") (pinfunction "PC12_80") (pintype "bidirectional"))
    )
    (net (code "59") (name "SDIO_CMD") (class "Default")
      (node (ref "SDCARD2") (pin "3") (pinfunction "DI_3") (pintype "bidirectional"))
      (node (ref "STM") (pin "83") (pinfunction "PD2_83") (pintype "bidirectional"))
    )
    (net (code "60") (name "SDIO_D0") (class "Default")
      (node (ref "SDCARD2") (pin "7") (pinfunction "DO_7") (pintype "bidirectional"))
      (node (ref "STM") (pin "65") (pinfunction "PC8_65") (pintype "bidirectional"))
    )
    (net (code "61") (name "SDIO_D1") (class "Default")
      (node (ref "SDCARD2") (pin "8") (pinfunction "RSV_8") (pintype "bidirectional"))
      (node (ref "STM") (pin "66") (pinfunction "PC9_66") (pintype "bidirectional"))
    )
    (net (code "62") (name "SDIO_D2") (class "Default")
      (node (ref "SDCARD2") (pin "1") (pinfunction "NC_1") (pintype "bidirectional"))
      (node (ref "STM") (pin "78") (pinfunction "PC10_78") (pintype "bidirectional"))
    )
    (net (code "63") (name "SDIO_D3") (class "Default")
      (node (ref "SDCARD2") (pin "2") (pinfunction "CS_2") (pintype "bidirectional"))
      (node (ref "STM") (pin "79") (pinfunction "PC11_79") (pintype "bidirectional"))
    )
    (net (code "64") (name "SDIO_DETECT") (class "Default")
      (node (ref "SDCARD2") (pin "CD2") (pinfunction "SHIELD_CD2") (pintype "bidirectional"))
      (node (ref "STM") (pin "84") (pinfunction "PD3_84") (pintype "bidirectional"))
    )
    (net (code "65") (name "SW_CLK") (class "Default")
      (node (ref "JP4") (pin "2") (pinfunction "2_2") (pintype "passive"))
      (node (ref "STM") (pin "76") (pinfunction "PA14_76") (pintype "bidirectional"))
    )
    (net (code "66") (name "SW_DIO") (class "Default")
      (node (ref "JP4") (pin "4") (pinfunction "4_4") (pintype "passive"))
      (node (ref "STM") (pin "72") (pinfunction "PA13_72") (pintype "bidirectional"))
    )
    (net (code "67") (name "TFT_BACKLIGHT") (class "Default")
      (node (ref "STM") (pin "60") (pinfunction "PD13_60") (pintype "bidirectional"))
      (node (ref "U$3") (pin "27") (pinfunction "BL_CNT_27") (pintype "bidirectional"))
    )
    (net (code "68") (name "TFT_CS") (class "Default")
      (node (ref "STM") (pin "88") (pinfunction "PD7_88") (pintype "bidirectional"))
      (node (ref "U$3") (pin "19") (pinfunction "CS_19") (pintype "bidirectional"))
    )
    (net (code "69") (name "TFT_D0") (class "Default")
      (node (ref "STM") (pin "61") (pinfunction "PD14_61") (pintype "bidirectional"))
      (node (ref "U$3") (pin "3") (pinfunction "D0_3") (pintype "bidirectional"))
    )
    (net (code "70") (name "TFT_D1") (class "Default")
      (node (ref "STM") (pin "62") (pinfunction "PD15_62") (pintype "bidirectional"))
      (node (ref "U$3") (pin "4") (pinfunction "D1_4") (pintype "bidirectional"))
    )
    (net (code "71") (name "TFT_D2") (class "Default")
      (node (ref "STM") (pin "81") (pinfunction "PD0_81") (pintype "bidirectional"))
      (node (ref "U$3") (pin "5") (pinfunction "D2_5") (pintype "bidirectional"))
    )
    (net (code "72") (name "TFT_D3") (class "Default")
      (node (ref "STM") (pin "82") (pinfunction "PD1_82") (pintype "bidirectional"))
      (node (ref "U$3") (pin "6") (pinfunction "D3_6") (pintype "bidirectional"))
    )
    (net (code "73") (name "TFT_D4") (class "Default")
      (node (ref "STM") (pin "38") (pinfunction "PE7_38") (pintype "bidirectional"))
      (node (ref "U$3") (pin "7") (pinfunction "D4_7") (pintype "bidirectional"))
    )
    (net (code "74") (name "TFT_D5") (class "Default")
      (node (ref "STM") (pin "39") (pinfunction "PE8_39") (pintype "bidirectional"))
      (node (ref "U$3") (pin "8") (pinfunction "D5_8") (pintype "bidirectional"))
    )
    (net (code "75") (name "TFT_D6") (class "Default")
      (node (ref "STM") (pin "40") (pinfunction "PE9_40") (pintype "bidirectional"))
      (node (ref "U$3") (pin "9") (pinfunction "D6_9") (pintype "bidirectional"))
    )
    (net (code "76") (name "TFT_D7") (class "Default")
      (node (ref "STM") (pin "41") (pinfunction "PE10_41") (pintype "bidirectional"))
      (node (ref "U$3") (pin "10") (pinfunction "D7_10") (pintype "bidirectional"))
    )
    (net (code "77") (name "TFT_D8") (class "Default")
      (node (ref "STM") (pin "42") (pinfunction "PE11_42") (pintype "bidirectional"))
      (node (ref "U$3") (pin "11") (pinfunction "D8_11") (pintype "bidirectional"))
    )
    (net (code "78") (name "TFT_D9") (class "Default")
      (node (ref "STM") (pin "43") (pinfunction "PE12_43") (pintype "bidirectional"))
      (node (ref "U$3") (pin "12") (pinfunction "D9_12") (pintype "bidirectional"))
    )
    (net (code "79") (name "TFT_D10") (class "Default")
      (node (ref "STM") (pin "44") (pinfunction "PE13_44") (pintype "bidirectional"))
      (node (ref "U$3") (pin "13") (pinfunction "D10_13") (pintype "bidirectional"))
    )
    (net (code "80") (name "TFT_D11") (class "Default")
      (node (ref "STM") (pin "45") (pinfunction "PE14_45") (pintype "bidirectional"))
      (node (ref "U$3") (pin "14") (pinfunction "D11_14") (pintype "bidirectional"))
    )
    (net (code "81") (name "TFT_D12") (class "Default")
      (node (ref "STM") (pin "46") (pinfunction "PE15_46") (pintype "bidirectional"))
      (node (ref "U$3") (pin "15") (pinfunction "D12_15") (pintype "bidirectional"))
    )
    (net (code "82") (name "TFT_D13") (class "Default")
      (node (ref "STM") (pin "55") (pinfunction "PD8_55") (pintype "bidirectional"))
      (node (ref "U$3") (pin "16") (pinfunction "D13_16") (pintype "bidirectional"))
    )
    (net (code "83") (name "TFT_D14") (class "Default")
      (node (ref "STM") (pin "56") (pinfunction "PD9_56") (pintype "bidirectional"))
      (node (ref "U$3") (pin "17") (pinfunction "D14_17") (pintype "bidirectional"))
    )
    (net (code "84") (name "TFT_D15") (class "Default")
      (node (ref "STM") (pin "57") (pinfunction "PD10_57") (pintype "bidirectional"))
      (node (ref "U$3") (pin "18") (pinfunction "D15_18") (pintype "bidirectional"))
    )
    (net (code "85") (name "TFT_RD") (class "Default")
      (node (ref "STM") (pin "85") (pinfunction "PD4_85") (pintype "bidirectional"))
      (node (ref "U$3") (pin "22") (pinfunction "RD_22") (pintype "bidirectional"))
    )
    (net (code "86") (name "TFT_RS") (class "Default")
      (node (ref "STM") (pin "58") (pinfunction "PD11_58") (pintype "bidirectional"))
      (node (ref "U$3") (pin "20") (pinfunction "RS_20") (pintype "bidirectional"))
    )
    (net (code "87") (name "TFT_WR") (class "Default")
      (node (ref "STM") (pin "86") (pinfunction "PD5_86") (pintype "bidirectional"))
      (node (ref "U$3") (pin "21") (pinfunction "WR_21") (pintype "bidirectional"))
    )
    (net (code "88") (name "TP_CS") (class "Default")
      (node (ref "STM") (pin "51") (pinfunction "PB12_51") (pintype "bidirectional"))
      (node (ref "U$3") (pin "29") (pinfunction "TP_CS_29") (pintype "bidirectional"))
    )
    (net (code "89") (name "TP_IQR") (class "Default")
      (node (ref "STM") (pin "59") (pinfunction "PD12_59") (pintype "bidirectional"))
      (node (ref "U$3") (pin "28") (pinfunction "TP_IRQ_28") (pintype "bidirectional"))
    )
    (net (code "90") (name "TP_SCK") (class "Default")
      (node (ref "STM") (pin "52") (pinfunction "PB13_52") (pintype "bidirectional"))
      (node (ref "U$3") (pin "30") (pinfunction "TP_SCK_30") (pintype "bidirectional"))
    )
    (net (code "91") (name "TP_SI") (class "Default")
      (node (ref "STM") (pin "54") (pinfunction "PB15_54") (pintype "bidirectional"))
      (node (ref "U$3") (pin "31") (pinfunction "TP_SI_31") (pintype "bidirectional"))
    )
    (net (code "92") (name "TP_SO") (class "Default")
      (node (ref "STM") (pin "53") (pinfunction "PB14_53") (pintype "bidirectional"))
      (node (ref "U$3") (pin "32") (pinfunction "TP_SO_32") (pintype "bidirectional"))
    )
    (net (code "93") (name "USART1_RX") (class "Default")
      (node (ref "STM") (pin "93") (pinfunction "PB7_93") (pintype "bidirectional"))
      (node (ref "U1") (pin "1") (pinfunction "TX_1") (pintype "bidirectional"))
    )
    (net (code "94") (name "USART1_TX") (class "Default")
      (node (ref "STM") (pin "92") (pinfunction "PB6_92") (pintype "bidirectional"))
      (node (ref "U1") (pin "2") (pinfunction "RX_2") (pintype "bidirectional"))
    )
    (net (code "95") (name "VCC") (class "Default")
      (node (ref "D2") (pin "A") (pinfunction "A_A") (pintype "passive"))
      (node (ref "X1") (pin "2") (pinfunction "KL_2") (pintype "passive"))
    )
    (net (code "96") (name "unconnected-(IC1-AUX_CL-Pad7)") (class "Default")
      (node (ref "IC1") (pin "7") (pinfunction "AUX_CL_7") (pintype "bidirectional"))
    )
    (net (code "97") (name "unconnected-(IC1-AUX_DA-Pad6)") (class "Default")
      (node (ref "IC1") (pin "6") (pinfunction "AUX_DA_6") (pintype "bidirectional"))
    )
    (net (code "98") (name "unconnected-(IC1-INT-Pad12)") (class "Default")
      (node (ref "IC1") (pin "12") (pinfunction "INT_12") (pintype "bidirectional"))
    )
    (net (code "99") (name "unconnected-(SDCARD2-SHIELD-PadCD1)") (class "Default")
      (node (ref "SDCARD2") (pin "CD1") (pinfunction "SHIELD_CD1") (pintype "bidirectional"))
    )
    (net (code "100") (name "unconnected-(STMD-PA11-Pad70)") (class "Default")
      (node (ref "STM") (pin "70") (pinfunction "PA11_70") (pintype "bidirectional"))
    )
    (net (code "101") (name "unconnected-(STMD-PA12-Pad71)") (class "Default")
      (node (ref "STM") (pin "71") (pinfunction "PA12_71") (pintype "bidirectional"))
    )
    (net (code "102") (name "unconnected-(STMI-PC6-Pad63)") (class "Default")
      (node (ref "STM") (pin "63") (pinfunction "PC6_63") (pintype "bidirectional"))
    )
    (net (code "103") (name "unconnected-(STMI-PC7-Pad64)") (class "Default")
      (node (ref "STM") (pin "64") (pinfunction "PC7_64") (pintype "bidirectional"))
    )
    (net (code "104") (name "unconnected-(STMK-PD6-Pad87)") (class "Default")
      (node (ref "STM") (pin "87") (pinfunction "PD6_87") (pintype "bidirectional"))
    )
    (net (code "105") (name "unconnected-(STMM-PE0-Pad97)") (class "Default")
      (node (ref "STM") (pin "97") (pinfunction "PE0_97") (pintype "bidirectional"))
    )
    (net (code "106") (name "unconnected-(STMM-PE1-Pad98)") (class "Default")
      (node (ref "STM") (pin "98") (pinfunction "PE1_98") (pintype "bidirectional"))
    )
    (net (code "107") (name "unconnected-(STMM-PE2-Pad1)") (class "Default")
      (node (ref "STM") (pin "1") (pinfunction "PE2_1") (pintype "bidirectional"))
    )
    (net (code "108") (name "unconnected-(STMM-PE3-Pad2)") (class "Default")
      (node (ref "STM") (pin "2") (pinfunction "PE3_2") (pintype "bidirectional"))
    )
    (net (code "109") (name "unconnected-(STMM-PE4-Pad3)") (class "Default")
      (node (ref "STM") (pin "3") (pinfunction "PE4_3") (pintype "bidirectional"))
    )
    (net (code "110") (name "unconnected-(STMM-PE5-Pad4)") (class "Default")
      (node (ref "STM") (pin "4") (pinfunction "PE5_4") (pintype "bidirectional"))
    )
    (net (code "111") (name "unconnected-(STMM-PE6-Pad5)") (class "Default")
      (node (ref "STM") (pin "5") (pinfunction "PE6_5") (pintype "bidirectional"))
    )
    (net (code "112") (name "unconnected-(U$3-3V3-Pad33)") (class "Default")
      (node (ref "U$3") (pin "33") (pinfunction "3V3_33") (pintype "bidirectional"))
    )
    (net (code "113") (name "unconnected-(U$3-NC-Pad24)") (class "Default")
      (node (ref "U$3") (pin "24") (pinfunction "NC_24") (pintype "bidirectional"))
    )
    (net (code "114") (name "unconnected-(U1-AIO0-Pad9)") (class "Default")
      (node (ref "U1") (pin "9") (pinfunction "AIO0_9") (pintype "bidirectional"))
    )
    (net (code "115") (name "unconnected-(U1-AIO1-Pad10)") (class "Default")
      (node (ref "U1") (pin "10") (pinfunction "AIO1_10") (pintype "bidirectional"))
    )
    (net (code "116") (name "unconnected-(U1-CLK-Pad19)") (class "Default")
      (node (ref "U1") (pin "19") (pinfunction "CLK_19") (pintype "bidirectional"))
    )
    (net (code "117") (name "unconnected-(U1-CSB-Pad16)") (class "Default")
      (node (ref "U1") (pin "16") (pinfunction "CSB_16") (pintype "bidirectional"))
    )
    (net (code "118") (name "unconnected-(U1-CTS-Pad3)") (class "Default")
      (node (ref "U1") (pin "3") (pinfunction "CTS_3") (pintype "bidirectional"))
    )
    (net (code "119") (name "unconnected-(U1-GND1-Pad21)") (class "Default")
      (node (ref "U1") (pin "21") (pinfunction "GND1_21") (pintype "bidirectional"))
    )
    (net (code "120") (name "unconnected-(U1-MISO-Pad18)") (class "Default")
      (node (ref "U1") (pin "18") (pinfunction "MISO_18") (pintype "bidirectional"))
    )
    (net (code "121") (name "unconnected-(U1-MOSI-Pad17)") (class "Default")
      (node (ref "U1") (pin "17") (pinfunction "MOSI_17") (pintype "bidirectional"))
    )
    (net (code "122") (name "unconnected-(U1-NC-Pad14)") (class "Default")
      (node (ref "U1") (pin "14") (pinfunction "NC_14") (pintype "bidirectional"))
    )
    (net (code "123") (name "unconnected-(U1-PCM_CLK-Pad5)") (class "Default")
      (node (ref "U1") (pin "5") (pinfunction "PCM_CLK_5") (pintype "bidirectional"))
    )
    (net (code "124") (name "unconnected-(U1-PCM_IN-Pad7)") (class "Default")
      (node (ref "U1") (pin "7") (pinfunction "PCM_IN_7") (pintype "bidirectional"))
    )
    (net (code "125") (name "unconnected-(U1-PCM_OUT-Pad6)") (class "Default")
      (node (ref "U1") (pin "6") (pinfunction "PCM_OUT_6") (pintype "bidirectional"))
    )
    (net (code "126") (name "unconnected-(U1-PCN_SYNC-Pad8)") (class "Default")
      (node (ref "U1") (pin "8") (pinfunction "PCN_SYNC_8") (pintype "bidirectional"))
    )
    (net (code "127") (name "unconnected-(U1-PIO0-Pad23)") (class "Default")
      (node (ref "U1") (pin "23") (pinfunction "PIO0_23") (pintype "bidirectional"))
    )
    (net (code "128") (name "unconnected-(U1-PIO1-Pad24)") (class "Default")
      (node (ref "U1") (pin "24") (pinfunction "PIO1_24") (pintype "bidirectional"))
    )
    (net (code "129") (name "unconnected-(U1-PIO2-Pad25)") (class "Default")
      (node (ref "U1") (pin "25") (pinfunction "PIO2_25") (pintype "bidirectional"))
    )
    (net (code "130") (name "unconnected-(U1-PIO3-Pad26)") (class "Default")
      (node (ref "U1") (pin "26") (pinfunction "PIO3_26") (pintype "bidirectional"))
    )
    (net (code "131") (name "unconnected-(U1-PIO4-Pad27)") (class "Default")
      (node (ref "U1") (pin "27") (pinfunction "PIO4_27") (pintype "bidirectional"))
    )
    (net (code "132") (name "unconnected-(U1-PIO5-Pad28)") (class "Default")
      (node (ref "U1") (pin "28") (pinfunction "PIO5_28") (pintype "bidirectional"))
    )
    (net (code "133") (name "unconnected-(U1-PIO6-Pad29)") (class "Default")
      (node (ref "U1") (pin "29") (pinfunction "PIO6_29") (pintype "bidirectional"))
    )
    (net (code "134") (name "unconnected-(U1-PIO7-Pad30)") (class "Default")
      (node (ref "U1") (pin "30") (pinfunction "PIO7_30") (pintype "bidirectional"))
    )
    (net (code "135") (name "unconnected-(U1-PIO8-Pad31)") (class "Default")
      (node (ref "U1") (pin "31") (pinfunction "PIO8_31") (pintype "bidirectional"))
    )
    (net (code "136") (name "unconnected-(U1-PIO9-Pad32)") (class "Default")
      (node (ref "U1") (pin "32") (pinfunction "PIO9_32") (pintype "bidirectional"))
    )
    (net (code "137") (name "unconnected-(U1-PIO10-Pad33)") (class "Default")
      (node (ref "U1") (pin "33") (pinfunction "PIO10_33") (pintype "bidirectional"))
    )
    (net (code "138") (name "unconnected-(U1-RST-Pad11)") (class "Default")
      (node (ref "U1") (pin "11") (pinfunction "RST_11") (pintype "bidirectional"))
    )
    (net (code "139") (name "unconnected-(U1-RTS-Pad4)") (class "Default")
      (node (ref "U1") (pin "4") (pinfunction "RTS_4") (pintype "bidirectional"))
    )
    (net (code "140") (name "unconnected-(U1-VBUSD+-Pad20)") (class "Default")
      (node (ref "U1") (pin "20") (pinfunction "VBUSD+_20") (pintype "bidirectional"))
    )
    (net (code "141") (name "unconnected-(U1-VBUSD--Pad15)") (class "Default")
      (node (ref "U1") (pin "15") (pinfunction "VBUSD-_15") (pintype "bidirectional"))
    )
  )
)
